# aw_401_powersupply.net
KiCad netlist of a schematic drawn in EAGLE
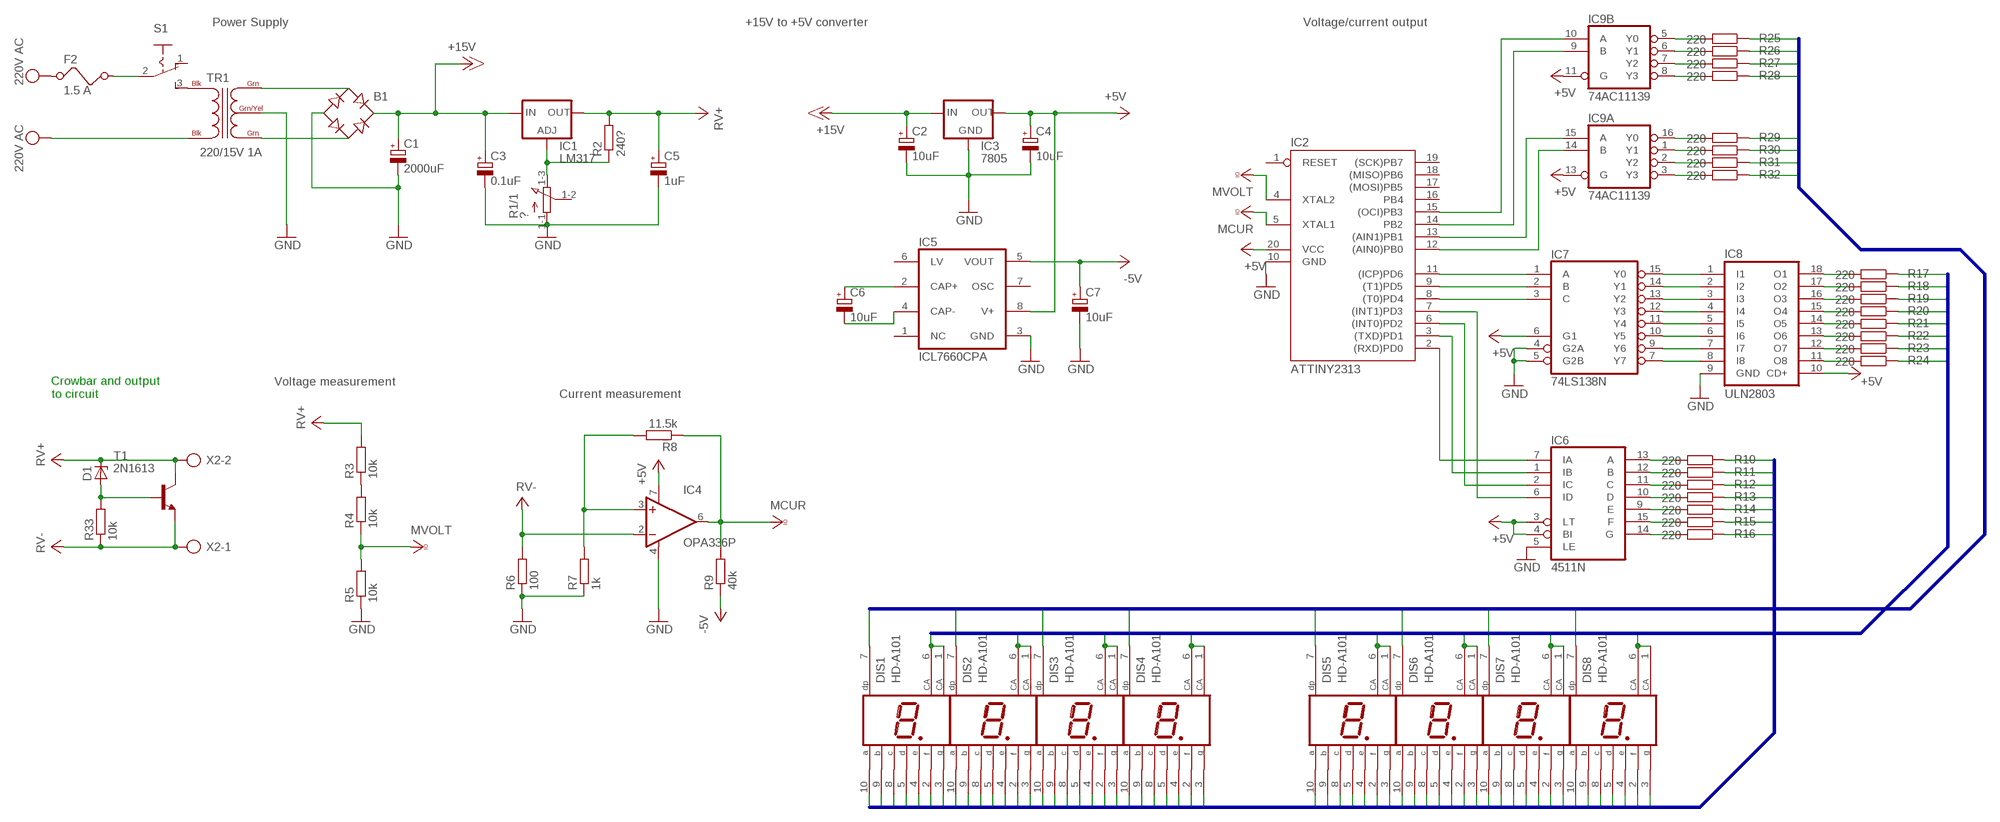
[diagram p0: schematic, sheet 1]

(export (version "E")
  (design (tool "Eeschema 10.0.6"))
  (components
    (comp (ref "B1")
      (value "RB1A")
      (footprint "eagle-import:RB1A")
      (libsource (lib "eagle-import") (part "RB1A"))
    )
    (comp (ref "C1")
      (value "2000uF")
      (footprint "eagle-import:E3,5-8")
      (libsource (lib "eagle-import") (part "CPOL-EUE3.5-8"))
    )
    (comp (ref "C2")
      (value "10uF")
      (footprint "eagle-import:E2,5-6")
      (libsource (lib "eagle-import") (part "CPOL-EUE2.5-6"))
    )
    (comp (ref "C3")
      (value "0.1uF")
      (footprint "eagle-import:E2,5-6")
      (libsource (lib "eagle-import") (part "CPOL-EUE2.5-6"))
    )
    (comp (ref "C4")
      (value "10uF")
      (footprint "eagle-import:E2,5-6")
      (libsource (lib "eagle-import") (part "CPOL-EUE2.5-6"))
    )
    (comp (ref "C5")
      (value "1uF")
      (footprint "eagle-import:E2,5-6")
      (libsource (lib "eagle-import") (part "CPOL-EUE2.5-6"))
    )
    (comp (ref "C6")
      (value "10uF")
      (footprint "eagle-import:E2,5-6")
      (libsource (lib "eagle-import") (part "CPOL-EUE2.5-6"))
    )
    (comp (ref "C7")
      (value "10uF")
      (footprint "eagle-import:E2,5-6")
      (libsource (lib "eagle-import") (part "CPOL-EUE2.5-6"))
    )
    (comp (ref "D1")
      (value "ZENER-DIODEC1702-15")
      (footprint "eagle-import:C1702-15")
      (libsource (lib "eagle-import") (part "ZENER-DIODEC1702-15"))
    )
    (comp (ref "DIS1")
      (value "HD-A101")
      (footprint "eagle-import:HDSP-A")
      (libsource (lib "eagle-import") (part "HD-A101"))
    )
    (comp (ref "DIS2")
      (value "HD-A101")
      (footprint "eagle-import:HDSP-A")
      (libsource (lib "eagle-import") (part "HD-A101"))
    )
    (comp (ref "DIS3")
      (value "HD-A101")
      (footprint "eagle-import:HDSP-A")
      (libsource (lib "eagle-import") (part "HD-A101"))
    )
    (comp (ref "DIS4")
      (value "HD-A101")
      (footprint "eagle-import:HDSP-A")
      (libsource (lib "eagle-import") (part "HD-A101"))
    )
    (comp (ref "DIS5")
      (value "HD-A101")
      (footprint "eagle-import:HDSP-A")
      (libsource (lib "eagle-import") (part "HD-A101"))
    )
    (comp (ref "DIS6")
      (value "HD-A101")
      (footprint "eagle-import:HDSP-A")
      (libsource (lib "eagle-import") (part "HD-A101"))
    )
    (comp (ref "DIS7")
      (value "HD-A101")
      (footprint "eagle-import:HDSP-A")
      (libsource (lib "eagle-import") (part "HD-A101"))
    )
    (comp (ref "DIS8")
      (value "HD-A101")
      (footprint "eagle-import:HDSP-A")
      (libsource (lib "eagle-import") (part "HD-A101"))
    )
    (comp (ref "F2")
      (value "1.5 A")
      (footprint "eagle-import:FUSE")
      (libsource (lib "eagle-import") (part "FUSE"))
    )
    (comp (ref "IC1")
      (value "LM317")
      (footprint "eagle-import:317TS")
      (libsource (lib "eagle-import") (part "LM317TS"))
    )
    (comp (ref "IC2")
      (value "ATTINY2313")
      (footprint "eagle-import:DIL20")
      (libsource (lib "eagle-import") (part "AT90S2313P"))
    )
    (comp (ref "IC3")
      (value "7805")
      (footprint "eagle-import:78XXS")
      (libsource (lib "eagle-import") (part "78XXS"))
    )
    (comp (ref "IC4")
      (value "OPA336P")
      (footprint "eagle-import:DIL08")
      (libsource (lib "eagle-import") (part "OPA336P"))
    )
    (comp (ref "IC5")
      (value "ICL7660CPA")
      (footprint "eagle-import:DIL08")
      (fields (field (name "MF") "INTERSIL"))
      (libsource (lib "eagle-import") (part "ICL7660CPA"))
    )
    (comp (ref "IC6")
      (value "4511N")
      (footprint "eagle-import:DIL16")
      (libsource (lib "eagle-import") (part "4511N"))
    )
    (comp (ref "IC7")
      (value "74LS138N")
      (footprint "eagle-import:DIL16")
      (libsource (lib "eagle-import") (part "74138NLS"))
    )
    (comp (ref "IC8")
      (value "ULN2803")
      (footprint "eagle-import:DIL18")
      (libsource (lib "eagle-import") (part "ULN2803A"))
    )
    (comp (ref "IC9")
      (value "74AC11139")
      (footprint "eagle-import:DIL16")
      (libsource (lib "eagle-import") (part "74AC11139"))
    )
    (comp (ref "R1")
      (value "?")
      (footprint "eagle-import:3RP_1610G")
      (libsource (lib "eagle-import") (part "3RP/1610G"))
    )
    (comp (ref "R2")
      (value "240?")
      (footprint "eagle-import:0207_10")
      (libsource (lib "eagle-import") (part "R-EU_0207/10"))
    )
    (comp (ref "R3")
      (value "10k")
      (footprint "eagle-import:0207_10")
      (libsource (lib "eagle-import") (part "R-EU_0207/10"))
    )
    (comp (ref "R4")
      (value "10k")
      (footprint "eagle-import:0207_10")
      (libsource (lib "eagle-import") (part "R-EU_0207/10"))
    )
    (comp (ref "R5")
      (value "10k")
      (footprint "eagle-import:0207_10")
      (libsource (lib "eagle-import") (part "R-EU_0207/10"))
    )
    (comp (ref "R6")
      (value "100")
      (footprint "eagle-import:0207_10")
      (libsource (lib "eagle-import") (part "R-EU_0207/10"))
    )
    (comp (ref "R7")
      (value "1k")
      (footprint "eagle-import:0207_10")
      (libsource (lib "eagle-import") (part "R-EU_0207/10"))
    )
    (comp (ref "R8")
      (value "11.5k")
      (footprint "eagle-import:0207_10")
      (libsource (lib "eagle-import") (part "R-EU_0207/10"))
    )
    (comp (ref "R9")
      (value "40k")
      (footprint "eagle-import:0207_10")
      (libsource (lib "eagle-import") (part "R-EU_0207/10"))
    )
    (comp (ref "R10")
      (value "220")
      (footprint "eagle-import:0207_10")
      (libsource (lib "eagle-import") (part "R-EU_0207/10"))
    )
    (comp (ref "R11")
      (value "220")
      (footprint "eagle-import:0207_10")
      (libsource (lib "eagle-import") (part "R-EU_0207/10"))
    )
    (comp (ref "R12")
      (value "220")
      (footprint "eagle-import:0207_10")
      (libsource (lib "eagle-import") (part "R-EU_0207/10"))
    )
    (comp (ref "R13")
      (value "220")
      (footprint "eagle-import:0207_10")
      (libsource (lib "eagle-import") (part "R-EU_0207/10"))
    )
    (comp (ref "R14")
      (value "220")
      (footprint "eagle-import:0207_10")
      (libsource (lib "eagle-import") (part "R-EU_0207/10"))
    )
    (comp (ref "R15")
      (value "220")
      (footprint "eagle-import:0207_10")
      (libsource (lib "eagle-import") (part "R-EU_0207/10"))
    )
    (comp (ref "R16")
      (value "220")
      (footprint "eagle-import:0207_10")
      (libsource (lib "eagle-import") (part "R-EU_0207/10"))
    )
    (comp (ref "R17")
      (value "220")
      (footprint "eagle-import:0207_10")
      (libsource (lib "eagle-import") (part "R-EU_0207/10"))
    )
    (comp (ref "R18")
      (value "220")
      (footprint "eagle-import:0207_10")
      (libsource (lib "eagle-import") (part "R-EU_0207/10"))
    )
    (comp (ref "R19")
      (value "220")
      (footprint "eagle-import:0207_10")
      (libsource (lib "eagle-import") (part "R-EU_0207/10"))
    )
    (comp (ref "R20")
      (value "220")
      (footprint "eagle-import:0207_10")
      (libsource (lib "eagle-import") (part "R-EU_0207/10"))
    )
    (comp (ref "R21")
      (value "220")
      (footprint "eagle-import:0207_10")
      (libsource (lib "eagle-import") (part "R-EU_0207/10"))
    )
    (comp (ref "R22")
      (value "220")
      (footprint "eagle-import:0207_10")
      (libsource (lib "eagle-import") (part "R-EU_0207/10"))
    )
    (comp (ref "R23")
      (value "220")
      (footprint "eagle-import:0207_10")
      (libsource (lib "eagle-import") (part "R-EU_0207/10"))
    )
    (comp (ref "R24")
      (value "220")
      (footprint "eagle-import:0207_10")
      (libsource (lib "eagle-import") (part "R-EU_0207/10"))
    )
    (comp (ref "R25")
      (value "220")
      (footprint "eagle-import:0207_10")
      (libsource (lib "eagle-import") (part "R-EU_0207/10"))
    )
    (comp (ref "R26")
      (value "220")
      (footprint "eagle-import:0207_10")
      (libsource (lib "eagle-import") (part "R-EU_0207/10"))
    )
    (comp (ref "R27")
      (value "220")
      (footprint "eagle-import:0207_10")
      (libsource (lib "eagle-import") (part "R-EU_0207/10"))
    )
    (comp (ref "R28")
      (value "220")
      (footprint "eagle-import:0207_10")
      (libsource (lib "eagle-import") (part "R-EU_0207/10"))
    )
    (comp (ref "R29")
      (value "220")
      (footprint "eagle-import:0207_10")
      (libsource (lib "eagle-import") (part "R-EU_0207/10"))
    )
    (comp (ref "R30")
      (value "220")
      (footprint "eagle-import:0207_10")
      (libsource (lib "eagle-import") (part "R-EU_0207/10"))
    )
    (comp (ref "R31")
      (value "220")
      (footprint "eagle-import:0207_10")
      (libsource (lib "eagle-import") (part "R-EU_0207/10"))
    )
    (comp (ref "R32")
      (value "220")
      (footprint "eagle-import:0207_10")
      (libsource (lib "eagle-import") (part "R-EU_0207/10"))
    )
    (comp (ref "R33")
      (value "10k")
      (footprint "eagle-import:0207_10")
      (libsource (lib "eagle-import") (part "R-EU_0207/10"))
    )
    (comp (ref "S1")
      (value "255SB")
      (footprint "eagle-import:255SB")
      (libsource (lib "eagle-import") (part "255SB"))
    )
    (comp (ref "T1")
      (value "2N1613")
      (footprint "eagle-import:TO5")
      (libsource (lib "eagle-import") (part "2N1613"))
    )
    (comp (ref "TR1")
      (value "220/15V 1A")
      (footprint "eagle-import:C2H")
      (libsource (lib "eagle-import") (part "166A24"))
    )
    (comp (ref "X2")
      (value "AK500/2")
      (footprint "eagle-import:AK500_2")
      (libsource (lib "eagle-import") (part "AK500/2"))
    )
  )
  (nets
    (net (code "1") (name "+5V") (class "Default")
      (node (ref "C4") (pin "+") (pinfunction "+_+") (pintype "passive"))
      (node (ref "IC2") (pin "20") (pinfunction "VCC_20") (pintype "power_in"))
      (node (ref "IC3") (pin "OUT") (pinfunction "OUT_OUT") (pintype "passive"))
      (node (ref "IC4") (pin "7") (pinfunction "V+_7") (pintype "power_in"))
      (node (ref "IC5") (pin "8") (pinfunction "V+_8") (pintype "power_in"))
      (node (ref "IC6") (pin "3") (pinfunction "LT_3") (pintype "input"))
      (node (ref "IC6") (pin "4") (pinfunction "BI_4") (pintype "input"))
      (node (ref "IC7") (pin "6") (pinfunction "G1_6") (pintype "input"))
      (node (ref "IC8") (pin "10") (pinfunction "CD+_10") (pintype "passive"))
      (node (ref "IC9") (pin "11") (pinfunction "G_11") (pintype "input"))
      (node (ref "IC9") (pin "13") (pinfunction "G_13") (pintype "input"))
    )
    (net (code "2") (name "+15V") (class "Default")
      (node (ref "B1") (pin "+") (pinfunction "+_+") (pintype "passive"))
      (node (ref "C1") (pin "+") (pinfunction "+_+") (pintype "passive"))
      (node (ref "C2") (pin "+") (pinfunction "+_+") (pintype "passive"))
      (node (ref "C3") (pin "+") (pinfunction "+_+") (pintype "passive"))
      (node (ref "IC1") (pin "3") (pinfunction "IN_3") (pintype "input"))
      (node (ref "IC3") (pin "IN") (pinfunction "IN_IN") (pintype "input"))
    )
    (net (code "3") (name "-5V") (class "Default")
      (node (ref "C7") (pin "+") (pinfunction "+_+") (pintype "passive"))
      (node (ref "IC5") (pin "5") (pinfunction "VOUT_5") (pintype "output"))
      (node (ref "R9") (pin "1") (pinfunction "1_1") (pintype "passive"))
    )
    (net (code "4") (name "/ANODE1") (class "Default")
      (node (ref "DIS8") (pin "1") (pinfunction "CA_1") (pintype "passive"))
      (node (ref "DIS8") (pin "6") (pinfunction "CA_6") (pintype "passive"))
      (node (ref "R17") (pin "1") (pinfunction "1_1") (pintype "passive"))
    )
    (net (code "5") (name "/ANODE2") (class "Default")
      (node (ref "DIS7") (pin "1") (pinfunction "CA_1") (pintype "passive"))
      (node (ref "DIS7") (pin "6") (pinfunction "CA_6") (pintype "passive"))
      (node (ref "R18") (pin "1") (pinfunction "1_1") (pintype "passive"))
    )
    (net (code "6") (name "/ANODE3") (class "Default")
      (node (ref "DIS6") (pin "1") (pinfunction "CA_1") (pintype "passive"))
      (node (ref "DIS6") (pin "6") (pinfunction "CA_6") (pintype "passive"))
      (node (ref "R19") (pin "1") (pinfunction "1_1") (pintype "passive"))
    )
    (net (code "7") (name "/ANODE4") (class "Default")
      (node (ref "DIS5") (pin "1") (pinfunction "CA_1") (pintype "passive"))
      (node (ref "DIS5") (pin "6") (pinfunction "CA_6") (pintype "passive"))
      (node (ref "R20") (pin "1") (pinfunction "1_1") (pintype "passive"))
    )
    (net (code "8") (name "/ANODE5") (class "Default")
      (node (ref "DIS4") (pin "1") (pinfunction "CA_1") (pintype "passive"))
      (node (ref "DIS4") (pin "6") (pinfunction "CA_6") (pintype "passive"))
      (node (ref "R21") (pin "1") (pinfunction "1_1") (pintype "passive"))
    )
    (net (code "9") (name "/ANODE6") (class "Default")
      (node (ref "DIS3") (pin "1") (pinfunction "CA_1") (pintype "passive"))
      (node (ref "DIS3") (pin "6") (pinfunction "CA_6") (pintype "passive"))
      (node (ref "R22") (pin "1") (pinfunction "1_1") (pintype "passive"))
    )
    (net (code "10") (name "/ANODE7") (class "Default")
      (node (ref "DIS2") (pin "1") (pinfunction "CA_1") (pintype "passive"))
      (node (ref "DIS2") (pin "6") (pinfunction "CA_6") (pintype "passive"))
      (node (ref "R23") (pin "1") (pinfunction "1_1") (pintype "passive"))
    )
    (net (code "11") (name "/ANODE8") (class "Default")
      (node (ref "DIS1") (pin "1") (pinfunction "CA_1") (pintype "passive"))
      (node (ref "DIS1") (pin "6") (pinfunction "CA_6") (pintype "passive"))
      (node (ref "R24") (pin "1") (pinfunction "1_1") (pintype "passive"))
    )
    (net (code "12") (name "/DP1") (class "Default")
      (node (ref "DIS1") (pin "7") (pinfunction "DP_7") (pintype "passive"))
      (node (ref "R32") (pin "1") (pinfunction "1_1") (pintype "passive"))
    )
    (net (code "13") (name "/DP2") (class "Default")
      (node (ref "DIS2") (pin "7") (pinfunction "DP_7") (pintype "passive"))
      (node (ref "R31") (pin "1") (pinfunction "1_1") (pintype "passive"))
    )
    (net (code "14") (name "/DP3") (class "Default")
      (node (ref "DIS3") (pin "7") (pinfunction "DP_7") (pintype "passive"))
      (node (ref "R30") (pin "1") (pinfunction "1_1") (pintype "passive"))
    )
    (net (code "15") (name "/DP4") (class "Default")
      (node (ref "DIS4") (pin "7") (pinfunction "DP_7") (pintype "passive"))
      (node (ref "R29") (pin "1") (pinfunction "1_1") (pintype "passive"))
    )
    (net (code "16") (name "/DP5") (class "Default")
      (node (ref "DIS5") (pin "7") (pinfunction "DP_7") (pintype "passive"))
      (node (ref "R28") (pin "1") (pinfunction "1_1") (pintype "passive"))
    )
    (net (code "17") (name "/DP6") (class "Default")
      (node (ref "DIS6") (pin "7") (pinfunction "DP_7") (pintype "passive"))
      (node (ref "R27") (pin "1") (pinfunction "1_1") (pintype "passive"))
    )
    (net (code "18") (name "/DP7") (class "Default")
      (node (ref "DIS7") (pin "7") (pinfunction "DP_7") (pintype "passive"))
      (node (ref "R26") (pin "1") (pinfunction "1_1") (pintype "passive"))
    )
    (net (code "19") (name "/DP8") (class "Default")
      (node (ref "DIS8") (pin "7") (pinfunction "DP_7") (pintype "passive"))
      (node (ref "R25") (pin "1") (pinfunction "1_1") (pintype "passive"))
    )
    (net (code "20") (name "/PORT0") (class "Default")
      (node (ref "DIS1") (pin "10") (pinfunction "A_10") (pintype "passive"))
      (node (ref "R10") (pin "1") (pinfunction "1_1") (pintype "passive"))
    )
    (net (code "21") (name "/PORT1") (class "Default")
      (node (ref "DIS1") (pin "9") (pinfunction "B_9") (pintype "passive"))
      (node (ref "R11") (pin "1") (pinfunction "1_1") (pintype "passive"))
    )
    (net (code "22") (name "/PORT2") (class "Default")
      (node (ref "DIS1") (pin "8") (pinfunction "C_8") (pintype "passive"))
      (node (ref "R12") (pin "1") (pinfunction "1_1") (pintype "passive"))
    )
    (net (code "23") (name "/PORT3") (class "Default")
      (node (ref "DIS1") (pin "5") (pinfunction "D_5") (pintype "passive"))
      (node (ref "R13") (pin "1") (pinfunction "1_1") (pintype "passive"))
    )
    (net (code "24") (name "/PORT4") (class "Default")
      (node (ref "DIS1") (pin "4") (pinfunction "E_4") (pintype "passive"))
      (node (ref "R14") (pin "1") (pinfunction "1_1") (pintype "passive"))
    )
    (net (code "25") (name "/PORT5") (class "Default")
      (node (ref "DIS1") (pin "2") (pinfunction "F_2") (pintype "passive"))
      (node (ref "R15") (pin "1") (pinfunction "1_1") (pintype "passive"))
    )
    (net (code "26") (name "/PORT6") (class "Default")
      (node (ref "DIS1") (pin "3") (pinfunction "G_3") (pintype "passive"))
      (node (ref "R16") (pin "1") (pinfunction "1_1") (pintype "passive"))
    )
    (net (code "27") (name "220V AC") (class "Default")
      (node (ref "F2") (pin "1") (pinfunction "1_1") (pintype "passive"))
      (node (ref "TR1") (pin "BLK@2") (pinfunction "BLK_BLK@2") (pintype "passive"))
    )
    (net (code "28") (name "GND") (class "Default")
      (node (ref "B1") (pin "-") (pinfunction "-_-") (pintype "passive"))
      (node (ref "C1") (pin "-") (pinfunction "-_-") (pintype "passive"))
      (node (ref "C2") (pin "-") (pinfunction "-_-") (pintype "passive"))
      (node (ref "C3") (pin "-") (pinfunction "-_-") (pintype "passive"))
      (node (ref "C4") (pin "-") (pinfunction "-_-") (pintype "passive"))
      (node (ref "C5") (pin "-") (pinfunction "-_-") (pintype "passive"))
      (node (ref "C7") (pin "-") (pinfunction "-_-") (pintype "passive"))
      (node (ref "IC2") (pin "10") (pinfunction "GND_10") (pintype "power_in"))
      (node (ref "IC3") (pin "GND") (pinfunction "GND_GND") (pintype "input"))
      (node (ref "IC4") (pin "4") (pinfunction "V-_4") (pintype "power_in"))
      (node (ref "IC5") (pin "3") (pinfunction "GND_3") (pintype "power_in"))
      (node (ref "IC6") (pin "5") (pinfunction "LE_5") (pintype "input"))
      (node (ref "IC7") (pin "4") (pinfunction "G2A_4") (pintype "input"))
      (node (ref "IC7") (pin "5") (pinfunction "G2B_5") (pintype "input"))
      (node (ref "IC8") (pin "9") (pinfunction "GND_9") (pintype "power_in"))
      (node (ref "R1") (pin "1-1") (pinfunction "A_1-1") (pintype "passive"))
      (node (ref "R5") (pin "1") (pinfunction "1_1") (pintype "passive"))
      (node (ref "R6") (pin "1") (pinfunction "1_1") (pintype "passive"))
      (node (ref "R7") (pin "1") (pinfunction "1_1") (pintype "passive"))
      (node (ref "TR1") (pin "GRN/YEL") (pinfunction "GRN/YEL_GRN/YEL") (pintype "passive"))
    )
    (net (code "29") (name "MCUR") (class "Default")
      (node (ref "IC2") (pin "4") (pinfunction "XTAL2_4") (pintype "bidirectional"))
      (node (ref "IC2") (pin "5") (pinfunction "XTAL1_5") (pintype "bidirectional"))
      (node (ref "IC4") (pin "6") (pinfunction "OUT_6") (pintype "output"))
      (node (ref "R4") (pin "1") (pinfunction "1_1") (pintype "passive"))
      (node (ref "R5") (pin "2") (pinfunction "2_2") (pintype "passive"))
      (node (ref "R8") (pin "1") (pinfunction "1_1") (pintype "passive"))
      (node (ref "R9") (pin "2") (pinfunction "2_2") (pintype "passive"))
    )
    (net (code "30") (name "Net-(B1-PadAC1)") (class "Default")
      (node (ref "B1") (pin "AC1") (pinfunction "AC1_AC1") (pintype "passive"))
      (node (ref "TR1") (pin "GRN@1") (pinfunction "GRN_GRN@1") (pintype "passive"))
    )
    (net (code "31") (name "Net-(B1-PadAC2)") (class "Default")
      (node (ref "B1") (pin "AC2") (pinfunction "AC2_AC2") (pintype "passive"))
      (node (ref "TR1") (pin "GRN@2") (pinfunction "GRN_GRN@2") (pintype "passive"))
    )
    (net (code "32") (name "Net-(IC1-ADJ)") (class "Default")
      (node (ref "IC1") (pin "1") (pinfunction "ADJ_1") (pintype "input"))
      (node (ref "R1") (pin "1-3") (pinfunction "E_1-3") (pintype "passive"))
      (node (ref "R2") (pin "1") (pinfunction "1_1") (pintype "passive"))
    )
    (net (code "33") (name "Net-(IC2-(AIN0)PB0)") (class "Default")
      (node (ref "IC2") (pin "12") (pinfunction "(AIN0)PB0_12") (pintype "bidirectional"))
      (node (ref "IC9") (pin "14") (pinfunction "B_14") (pintype "input"))
    )
    (net (code "34") (name "Net-(IC2-(AIN1)PB1)") (class "Default")
      (node (ref "IC2") (pin "13") (pinfunction "(AIN1)PB1_13") (pintype "bidirectional"))
      (node (ref "IC9") (pin "15") (pinfunction "A_15") (pintype "input"))
    )
    (net (code "35") (name "Net-(IC2-(ICP)PD6)") (class "Default")
      (node (ref "IC2") (pin "11") (pinfunction "(ICP)PD6_11") (pintype "bidirectional"))
      (node (ref "IC7") (pin "1") (pinfunction "A_1") (pintype "input"))
    )
    (net (code "36") (name "Net-(IC2-(INT0)PD2)") (class "Default")
      (node (ref "IC2") (pin "6") (pinfunction "(INT0)PD2_6") (pintype "bidirectional"))
      (node (ref "IC6") (pin "2") (pinfunction "IC_2") (pintype "input"))
    )
    (net (code "37") (name "Net-(IC2-(INT1)PD3)") (class "Default")
      (node (ref "IC2") (pin "7") (pinfunction "(INT1)PD3_7") (pintype "bidirectional"))
      (node (ref "IC6") (pin "6") (pinfunction "ID_6") (pintype "input"))
    )
    (net (code "38") (name "Net-(IC2-(OCI)PB3)") (class "Default")
      (node (ref "IC2") (pin "15") (pinfunction "(OCI)PB3_15") (pintype "bidirectional"))
      (node (ref "IC9") (pin "10") (pinfunction "A_10") (pintype "input"))
    )
    (net (code "39") (name "Net-(IC2-(RXD)PD0)") (class "Default")
      (node (ref "IC2") (pin "2") (pinfunction "(RXD)PD0_2") (pintype "bidirectional"))
      (node (ref "IC6") (pin "7") (pinfunction "IA_7") (pintype "input"))
    )
    (net (code "40") (name "Net-(IC2-(T0)PD4)") (class "Default")
      (node (ref "IC2") (pin "8") (pinfunction "(T0)PD4_8") (pintype "bidirectional"))
      (node (ref "IC7") (pin "3") (pinfunction "C_3") (pintype "input"))
    )
    (net (code "41") (name "Net-(IC2-(T1)PD5)") (class "Default")
      (node (ref "IC2") (pin "9") (pinfunction "(T1)PD5_9") (pintype "bidirectional"))
      (node (ref "IC7") (pin "2") (pinfunction "B_2") (pintype "input"))
    )
    (net (code "42") (name "Net-(IC2-(TXD)PD1)") (class "Default")
      (node (ref "IC2") (pin "3") (pinfunction "(TXD)PD1_3") (pintype "bidirectional"))
      (node (ref "IC6") (pin "1") (pinfunction "IB_1") (pintype "input"))
    )
    (net (code "43") (name "Net-(IC2-PB2)") (class "Default")
      (node (ref "IC2") (pin "14") (pinfunction "PB2_14") (pintype "bidirectional"))
      (node (ref "IC9") (pin "9") (pinfunction "B_9") (pintype "input"))
    )
    (net (code "44") (name "Net-(IC4-+IN)") (class "Default")
      (node (ref "IC4") (pin "3") (pinfunction "+IN_3") (pintype "input"))
      (node (ref "R7") (pin "2") (pinfunction "2_2") (pintype "passive"))
      (node (ref "R8") (pin "2") (pinfunction "2_2") (pintype "passive"))
    )
    (net (code "45") (name "Net-(IC5-CAP+)") (class "Default")
      (node (ref "C6") (pin "+") (pinfunction "+_+") (pintype "passive"))
      (node (ref "IC5") (pin "2") (pinfunction "CAP+_2") (pintype "passive"))
    )
    (net (code "46") (name "Net-(IC5-CAP-)") (class "Default")
      (node (ref "C6") (pin "-") (pinfunction "-_-") (pintype "passive"))
      (node (ref "IC5") (pin "4") (pinfunction "CAP-_4") (pintype "passive"))
    )
    (net (code "47") (name "Net-(IC6A-A)") (class "Default")
      (node (ref "IC6") (pin "13") (pinfunction "A_13") (pintype "output"))
      (node (ref "R10") (pin "2") (pinfunction "2_2") (pintype "passive"))
    )
    (net (code "48") (name "Net-(IC6A-B)") (class "Default")
      (node (ref "IC6") (pin "12") (pinfunction "B_12") (pintype "output"))
      (node (ref "R11") (pin "2") (pinfunction "2_2") (pintype "passive"))
    )
    (net (code "49") (name "Net-(IC6A-C)") (class "Default")
      (node (ref "IC6") (pin "11") (pinfunction "C_11") (pintype "output"))
      (node (ref "R12") (pin "2") (pinfunction "2_2") (pintype "passive"))
    )
    (net (code "50") (name "Net-(IC6A-D)") (class "Default")
      (node (ref "IC6") (pin "10") (pinfunction "D_10") (pintype "output"))
      (node (ref "R13") (pin "2") (pinfunction "2_2") (pintype "passive"))
    )
    (net (code "51") (name "Net-(IC6A-E)") (class "Default")
      (node (ref "IC6") (pin "9") (pinfunction "E_9") (pintype "output"))
      (node (ref "R14") (pin "2") (pinfunction "2_2") (pintype "passive"))
    )
    (net (code "52") (name "Net-(IC6A-F)") (class "Default")
      (node (ref "IC6") (pin "15") (pinfunction "F_15") (pintype "output"))
      (node (ref "R15") (pin "2") (pinfunction "2_2") (pintype "passive"))
    )
    (net (code "53") (name "Net-(IC6A-G)") (class "Default")
      (node (ref "IC6") (pin "14") (pinfunction "G_14") (pintype "output"))
      (node (ref "R16") (pin "2") (pinfunction "2_2") (pintype "passive"))
    )
    (net (code "54") (name "Net-(IC7A-Y0)") (class "Default")
      (node (ref "IC7") (pin "15") (pinfunction "Y0_15") (pintype "output"))
      (node (ref "IC8") (pin "1") (pinfunction "I1_1") (pintype "input"))
    )
    (net (code "55") (name "Net-(IC7A-Y1)") (class "Default")
      (node (ref "IC7") (pin "14") (pinfunction "Y1_14") (pintype "output"))
      (node (ref "IC8") (pin "2") (pinfunction "I2_2") (pintype "input"))
    )
    (net (code "56") (name "Net-(IC7A-Y2)") (class "Default")
      (node (ref "IC7") (pin "13") (pinfunction "Y2_13") (pintype "output"))
      (node (ref "IC8") (pin "3") (pinfunction "I3_3") (pintype "input"))
    )
    (net (code "57") (name "Net-(IC7A-Y3)") (class "Default")
      (node (ref "IC7") (pin "12") (pinfunction "Y3_12") (pintype "output"))
      (node (ref "IC8") (pin "4") (pinfunction "I4_4") (pintype "input"))
    )
    (net (code "58") (name "Net-(IC7A-Y4)") (class "Default")
      (node (ref "IC7") (pin "11") (pinfunction "Y4_11") (pintype "output"))
      (node (ref "IC8") (pin "5") (pinfunction "I5_5") (pintype "input"))
    )
    (net (code "59") (name "Net-(IC7A-Y5)") (class "Default")
      (node (ref "IC7") (pin "10") (pinfunction "Y5_10") (pintype "output"))
      (node (ref "IC8") (pin "6") (pinfunction "I6_6") (pintype "input"))
    )
    (net (code "60") (name "Net-(IC7A-Y6)") (class "Default")
      (node (ref "IC7") (pin "9") (pinfunction "Y6_9") (pintype "output"))
      (node (ref "IC8") (pin "7") (pinfunction "I7_7") (pintype "input"))
    )
    (net (code "61") (name "Net-(IC7A-Y7)") (class "Default")
      (node (ref "IC7") (pin "7") (pinfunction "Y7_7") (pintype "output"))
      (node (ref "IC8") (pin "8") (pinfunction "I8_8") (pintype "input"))
    )
    (net (code "62") (name "Net-(IC8-O1)") (class "Default")
      (node (ref "IC8") (pin "18") (pinfunction "O1_18") (pintype "open_collector"))
      (node (ref "R17") (pin "2") (pinfunction "2_2") (pintype "passive"))
    )
    (net (code "63") (name "Net-(IC8-O2)") (class "Default")
      (node (ref "IC8") (pin "17") (pinfunction "O2_17") (pintype "open_collector"))
      (node (ref "R18") (pin "2") (pinfunction "2_2") (pintype "passive"))
    )
    (net (code "64") (name "Net-(IC8-O3)") (class "Default")
      (node (ref "IC8") (pin "16") (pinfunction "O3_16") (pintype "open_collector"))
      (node (ref "R19") (pin "2") (pinfunction "2_2") (pintype "passive"))
    )
    (net (code "65") (name "Net-(IC8-O4)") (class "Default")
      (node (ref "IC8") (pin "15") (pinfunction "O4_15") (pintype "open_collector"))
      (node (ref "R20") (pin "2") (pinfunction "2_2") (pintype "passive"))
    )
    (net (code "66") (name "Net-(IC8-O5)") (class "Default")
      (node (ref "IC8") (pin "14") (pinfunction "O5_14") (pintype "open_collector"))
      (node (ref "R21") (pin "2") (pinfunction "2_2") (pintype "passive"))
    )
    (net (code "67") (name "Net-(IC8-O6)") (class "Default")
      (node (ref "IC8") (pin "13") (pinfunction "O6_13") (pintype "open_collector"))
      (node (ref "R22") (pin "2") (pinfunction "2_2") (pintype "passive"))
    )
    (net (code "68") (name "Net-(IC8-O7)") (class "Default")
      (node (ref "IC8") (pin "12") (pinfunction "O7_12") (pintype "open_collector"))
      (node (ref "R23") (pin "2") (pinfunction "2_2") (pintype "passive"))
    )
    (net (code "69") (name "Net-(IC8-O8)") (class "Default")
      (node (ref "IC8") (pin "11") (pinfunction "O8_11") (pintype "open_collector"))
      (node (ref "R24") (pin "2") (pinfunction "2_2") (pintype "passive"))
    )
    (net (code "70") (name "Net-(IC9A-Y0)") (class "Default")
      (node (ref "IC9") (pin "16") (pinfunction "Y0_16") (pintype "output"))
      (node (ref "R29") (pin "2") (pinfunction "2_2") (pintype "passive"))
    )
    (net (code "71") (name "Net-(IC9A-Y1)") (class "Default")
      (node (ref "IC9") (pin "1") (pinfunction "Y1_1") (pintype "output"))
      (node (ref "R30") (pin "2") (pinfunction "2_2") (pintype "passive"))
    )
    (net (code "72") (name "Net-(IC9A-Y2)") (class "Default")
      (node (ref "IC9") (pin "2") (pinfunction "Y2_2") (pintype "output"))
      (node (ref "R31") (pin "2") (pinfunction "2_2") (pintype "passive"))
    )
    (net (code "73") (name "Net-(IC9A-Y3)") (class "Default")
      (node (ref "IC9") (pin "3") (pinfunction "Y3_3") (pintype "output"))
      (node (ref "R32") (pin "2") (pinfunction "2_2") (pintype "passive"))
    )
    (net (code "74") (name "Net-(IC9B-Y0)") (class "Default")
      (node (ref "IC9") (pin "5") (pinfunction "Y0_5") (pintype "output"))
      (node (ref "R25") (pin "2") (pinfunction "2_2") (pintype "passive"))
    )
    (net (code "75") (name "Net-(IC9B-Y1)") (class "Default")
      (node (ref "IC9") (pin "6") (pinfunction "Y1_6") (pintype "output"))
      (node (ref "R26") (pin "2") (pinfunction "2_2") (pintype "passive"))
    )
    (net (code "76") (name "Net-(IC9B-Y2)") (class "Default")
      (node (ref "IC9") (pin "7") (pinfunction "Y2_7") (pintype "output"))
      (node (ref "R27") (pin "2") (pinfunction "2_2") (pintype "passive"))
    )
    (net (code "77") (name "Net-(IC9B-Y3)") (class "Default")
      (node (ref "IC9") (pin "8") (pinfunction "Y3_8") (pintype "output"))
      (node (ref "R28") (pin "2") (pinfunction "2_2") (pintype "passive"))
    )
    (net (code "78") (name "Net-(R3-Pad1)") (class "Default")
      (node (ref "R3") (pin "1") (pinfunction "1_1") (pintype "passive"))
      (node (ref "R4") (pin "2") (pinfunction "2_2") (pintype "passive"))
    )
    (net (code "79") (name "Net-(S1-P)") (class "Default")
      (node (ref "F2") (pin "2") (pinfunction "2_2") (pintype "passive"))
      (node (ref "S1") (pin "2") (pinfunction "P_2") (pintype "passive"))
    )
    (net (code "80") (name "Net-(S1-S)") (class "Default")
      (node (ref "S1") (pin "3") (pinfunction "S_3") (pintype "passive"))
      (node (ref "TR1") (pin "BLK@1") (pinfunction "BLK_BLK@1") (pintype "passive"))
    )
    (net (code "81") (name "Net-(T1-B)") (class "Default")
      (node (ref "D1") (pin "A") (pinfunction "A_A") (pintype "passive"))
      (node (ref "R33") (pin "2") (pinfunction "2_2") (pintype "passive"))
      (node (ref "T1") (pin "2") (pinfunction "B_2") (pintype "passive"))
    )
    (net (code "82") (name "RV+") (class "Default")
      (node (ref "C5") (pin "+") (pinfunction "+_+") (pintype "passive"))
      (node (ref "D1") (pin "C") (pinfunction "C_C") (pintype "passive"))
      (node (ref "IC1") (pin "2") (pinfunction "OUT_2") (pintype "passive"))
      (node (ref "IC4") (pin "2") (pinfunction "-IN_2") (pintype "input"))
      (node (ref "R2") (pin "2") (pinfunction "2_2") (pintype "passive"))
      (node (ref "R3") (pin "2") (pinfunction "2_2") (pintype "passive"))
      (node (ref "R33") (pin "1") (pinfunction "1_1") (pintype "passive"))
      (node (ref "R6") (pin "2") (pinfunction "2_2") (pintype "passive"))
      (node (ref "T1") (pin "1") (pinfunction "E_1") (pintype "passive"))
      (node (ref "T1") (pin "3") (pinfunction "C_3") (pintype "passive"))
      (node (ref "X2") (pin "1") (pinfunction "KL_1") (pintype "passive"))
      (node (ref "X2") (pin "2") (pinfunction "KL_2") (pintype "passive"))
    )
    (net (code "83") (name "unconnected-(DIS2-A-Pad10)") (class "Default")
      (node (ref "DIS2") (pin "10") (pinfunction "A_10") (pintype "passive"))
    )
    (net (code "84") (name "unconnected-(DIS2-B-Pad9)") (class "Default")
      (node (ref "DIS2") (pin "9") (pinfunction "B_9") (pintype "passive"))
    )
    (net (code "85") (name "unconnected-(DIS2-C-Pad8)") (class "Default")
      (node (ref "DIS2") (pin "8") (pinfunction "C_8") (pintype "passive"))
    )
    (net (code "86") (name "unconnected-(DIS2-D-Pad5)") (class "Default")
      (node (ref "DIS2") (pin "5") (pinfunction "D_5") (pintype "passive"))
    )
    (net (code "87") (name "unconnected-(DIS2-E-Pad4)") (class "Default")
      (node (ref "DIS2") (pin "4") (pinfunction "E_4") (pintype "passive"))
    )
    (net (code "88") (name "unconnected-(DIS2-F-Pad2)") (class "Default")
      (node (ref "DIS2") (pin "2") (pinfunction "F_2") (pintype "passive"))
    )
    (net (code "89") (name "unconnected-(DIS2-G-Pad3)") (class "Default")
      (node (ref "DIS2") (pin "3") (pinfunction "G_3") (pintype "passive"))
    )
    (net (code "90") (name "unconnected-(DIS3-A-Pad10)") (class "Default")
      (node (ref "DIS3") (pin "10") (pinfunction "A_10") (pintype "passive"))
    )
    (net (code "91") (name "unconnected-(DIS3-B-Pad9)") (class "Default")
      (node (ref "DIS3") (pin "9") (pinfunction "B_9") (pintype "passive"))
    )
    (net (code "92") (name "unconnected-(DIS3-C-Pad8)") (class "Default")
      (node (ref "DIS3") (pin "8") (pinfunction "C_8") (pintype "passive"))
    )
    (net (code "93") (name "unconnected-(DIS3-D-Pad5)") (class "Default")
      (node (ref "DIS3") (pin "5") (pinfunction "D_5") (pintype "passive"))
    )
    (net (code "94") (name "unconnected-(DIS3-E-Pad4)") (class "Default")
      (node (ref "DIS3") (pin "4") (pinfunction "E_4") (pintype "passive"))
    )
    (net (code "95") (name "unconnected-(DIS3-F-Pad2)") (class "Default")
      (node (ref "DIS3") (pin "2") (pinfunction "F_2") (pintype "passive"))
    )
    (net (code "96") (name "unconnected-(DIS3-G-Pad3)") (class "Default")
      (node (ref "DIS3") (pin "3") (pinfunction "G_3") (pintype "passive"))
    )
    (net (code "97") (name "unconnected-(DIS4-A-Pad10)") (class "Default")
      (node (ref "DIS4") (pin "10") (pinfunction "A_10") (pintype "passive"))
    )
    (net (code "98") (name "unconnected-(DIS4-B-Pad9)") (class "Default")
      (node (ref "DIS4") (pin "9") (pinfunction "B_9") (pintype "passive"))
    )
    (net (code "99") (name "unconnected-(DIS4-C-Pad8)") (class "Default")
      (node (ref "DIS4") (pin "8") (pinfunction "C_8") (pintype "passive"))
    )
    (net (code "100") (name "unconnected-(DIS4-D-Pad5)") (class "Default")
      (node (ref "DIS4") (pin "5") (pinfunction "D_5") (pintype "passive"))
    )
    (net (code "101") (name "unconnected-(DIS4-E-Pad4)") (class "Default")
      (node (ref "DIS4") (pin "4") (pinfunction "E_4") (pintype "passive"))
    )
    (net (code "102") (name "unconnected-(DIS4-F-Pad2)") (class "Default")
      (node (ref "DIS4") (pin "2") (pinfunction "F_2") (pintype "passive"))
    )
    (net (code "103") (name "unconnected-(DIS4-G-Pad3)") (class "Default")
      (node (ref "DIS4") (pin "3") (pinfunction "G_3") (pintype "passive"))
    )
    (net (code "104") (name "unconnected-(DIS5-A-Pad10)") (class "Default")
      (node (ref "DIS5") (pin "10") (pinfunction "A_10") (pintype "passive"))
    )
    (net (code "105") (name "unconnected-(DIS5-B-Pad9)") (class "Default")
      (node (ref "DIS5") (pin "9") (pinfunction "B_9") (pintype "passive"))
    )
    (net (code "106") (name "unconnected-(DIS5-C-Pad8)") (class "Default")
      (node (ref "DIS5") (pin "8") (pinfunction "C_8") (pintype "passive"))
    )
    (net (code "107") (name "unconnected-(DIS5-D-Pad5)") (class "Default")
      (node (ref "DIS5") (pin "5") (pinfunction "D_5") (pintype "passive"))
    )
    (net (code "108") (name "unconnected-(DIS5-E-Pad4)") (class "Default")
      (node (ref "DIS5") (pin "4") (pinfunction "E_4") (pintype "passive"))
    )
    (net (code "109") (name "unconnected-(DIS5-F-Pad2)") (class "Default")
      (node (ref "DIS5") (pin "2") (pinfunction "F_2") (pintype "passive"))
    )
    (net (code "110") (name "unconnected-(DIS5-G-Pad3)") (class "Default")
      (node (ref "DIS5") (pin "3") (pinfunction "G_3") (pintype "passive"))
    )
    (net (code "111") (name "unconnected-(DIS6-A-Pad10)") (class "Default")
      (node (ref "DIS6") (pin "10") (pinfunction "A_10") (pintype "passive"))
    )
    (net (code "112") (name "unconnected-(DIS6-B-Pad9)") (class "Default")
      (node (ref "DIS6") (pin "9") (pinfunction "B_9") (pintype "passive"))
    )
    (net (code "113") (name "unconnected-(DIS6-C-Pad8)") (class "Default")
      (node (ref "DIS6") (pin "8") (pinfunction "C_8") (pintype "passive"))
    )
    (net (code "114") (name "unconnected-(DIS6-D-Pad5)") (class "Default")
      (node (ref "DIS6") (pin "5") (pinfunction "D_5") (pintype "passive"))
    )
    (net (code "115") (name "unconnected-(DIS6-E-Pad4)") (class "Default")
      (node (ref "DIS6") (pin "4") (pinfunction "E_4") (pintype "passive"))
    )
    (net (code "116") (name "unconnected-(DIS6-F-Pad2)") (class "Default")
      (node (ref "DIS6") (pin "2") (pinfunction "F_2") (pintype "passive"))
    )
    (net (code "117") (name "unconnected-(DIS6-G-Pad3)") (class "Default")
      (node (ref "DIS6") (pin "3") (pinfunction "G_3") (pintype "passive"))
    )
    (net (code "118") (name "unconnected-(DIS7-A-Pad10)") (class "Default")
      (node (ref "DIS7") (pin "10") (pinfunction "A_10") (pintype "passive"))
    )
    (net (code "119") (name "unconnected-(DIS7-B-Pad9)") (class "Default")
      (node (ref "DIS7") (pin "9") (pinfunction "B_9") (pintype "passive"))
    )
    (net (code "120") (name "unconnected-(DIS7-C-Pad8)") (class "Default")
      (node (ref "DIS7") (pin "8") (pinfunction "C_8") (pintype "passive"))
    )
    (net (code "121") (name "unconnected-(DIS7-D-Pad5)") (class "Default")
      (node (ref "DIS7") (pin "5") (pinfunction "D_5") (pintype "passive"))
    )
    (net (code "122") (name "unconnected-(DIS7-E-Pad4)") (class "Default")
      (node (ref "DIS7") (pin "4") (pinfunction "E_4") (pintype "passive"))
    )
    (net (code "123") (name "unconnected-(DIS7-F-Pad2)") (class "Default")
      (node (ref "DIS7") (pin "2") (pinfunction "F_2") (pintype "passive"))
    )
    (net (code "124") (name "unconnected-(DIS7-G-Pad3)") (class "Default")
      (node (ref "DIS7") (pin "3") (pinfunction "G_3") (pintype "passive"))
    )
    (net (code "125") (name "unconnected-(DIS8-A-Pad10)") (class "Default")
      (node (ref "DIS8") (pin "10") (pinfunction "A_10") (pintype "passive"))
    )
    (net (code "126") (name "unconnected-(DIS8-B-Pad9)") (class "Default")
      (node (ref "DIS8") (pin "9") (pinfunction "B_9") (pintype "passive"))
    )
    (net (code "127") (name "unconnected-(DIS8-C-Pad8)") (class "Default")
      (node (ref "DIS8") (pin "8") (pinfunction "C_8") (pintype "passive"))
    )
    (net (code "128") (name "unconnected-(DIS8-D-Pad5)") (class "Default")
      (node (ref "DIS8") (pin "5") (pinfunction "D_5") (pintype "passive"))
    )
    (net (code "129") (name "unconnected-(DIS8-E-Pad4)") (class "Default")
      (node (ref "DIS8") (pin "4") (pinfunction "E_4") (pintype "passive"))
    )
    (net (code "130") (name "unconnected-(DIS8-F-Pad2)") (class "Default")
      (node (ref "DIS8") (pin "2") (pinfunction "F_2") (pintype "passive"))
    )
    (net (code "131") (name "unconnected-(DIS8-G-Pad3)") (class "Default")
      (node (ref "DIS8") (pin "3") (pinfunction "G_3") (pintype "passive"))
    )
    (net (code "132") (name "unconnected-(IC2-(MISO)PB6-Pad18)") (class "Default")
      (node (ref "IC2") (pin "18") (pinfunction "(MISO)PB6_18") (pintype "bidirectional"))
    )
    (net (code "133") (name "unconnected-(IC2-(MOSI)PB5-Pad17)") (class "Default")
      (node (ref "IC2") (pin "17") (pinfunction "(MOSI)PB5_17") (pintype "bidirectional"))
    )
    (net (code "134") (name "unconnected-(IC2-(SCK)PB7-Pad19)") (class "Default")
      (node (ref "IC2") (pin "19") (pinfunction "(SCK)PB7_19") (pintype "bidirectional"))
    )
    (net (code "135") (name "unconnected-(IC2-PB4-Pad16)") (class "Default")
      (node (ref "IC2") (pin "16") (pinfunction "PB4_16") (pintype "bidirectional"))
    )
    (net (code "136") (name "unconnected-(IC2-RESET-Pad1)") (class "Default")
      (node (ref "IC2") (pin "1") (pinfunction "RESET_1") (pintype "bidirectional"))
    )
    (net (code "137") (name "unconnected-(IC5-LV-Pad6)") (class "Default")
      (node (ref "IC5") (pin "6") (pinfunction "LV_6") (pintype "passive"))
    )
    (net (code "138") (name "unconnected-(IC5-NC-Pad1)") (class "Default")
      (node (ref "IC5") (pin "1") (pinfunction "NC_1") (pintype "no_connect"))
    )
    (net (code "139") (name "unconnected-(IC5-OSC-Pad7)") (class "Default")
      (node (ref "IC5") (pin "7") (pinfunction "OSC_7") (pintype "output"))
    )
    (net (code "140") (name "unconnected-(R1A-S-Pad1-2)") (class "Default")
      (node (ref "R1") (pin "1-2") (pinfunction "S_1-2") (pintype "passive"))
    )
    (net (code "141") (name "unconnected-(S1-O-Pad1)") (class "Default")
      (node (ref "S1") (pin "1") (pinfunction "O_1") (pintype "passive"))
    )
  )
)
